# LPCB224_-_POWER_INPUT.net
KiCad netlist of a schematic drawn in Altium Designer
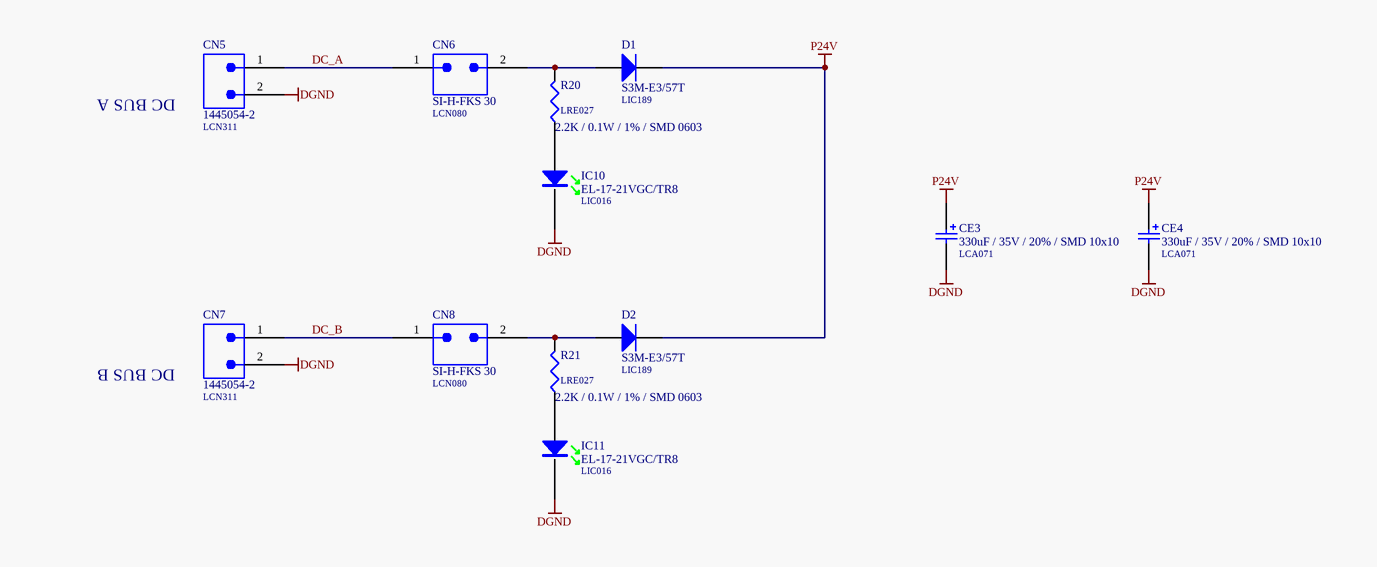
[diagram p0: LPCB224 - POWER INPUT.SchDoc]

(export (version "E")
  (design (tool "Eeschema 10.0.6"))
  (components
    (comp (ref "CE3")
      (value "330uF / 35V / 20% / SMD 10x10")
      (footprint "LFP041__NICHICON_WT_10X10")
      (description "Capacitor, Aluminum Electrolytic, 330uF, 35V, 20%, SMD (10mm x 10mm) [LCA071]")
      (fields (field (name "LDL_NUMBER") "LCA071"))
      (libsource (lib "LDL_Capacitors") (part "330uF / 35V / 20% / SMD 10x10"))
    )
    (comp (ref "CE4")
      (value "330uF / 35V / 20% / SMD 10x10")
      (footprint "LFP041__NICHICON_WT_10X10")
      (description "Capacitor, Aluminum Electrolytic, 330uF, 35V, 20%, SMD (10mm x 10mm) [LCA071]")
      (fields (field (name "LDL_NUMBER") "LCA071"))
      (libsource (lib "LDL_Capacitors") (part "330uF / 35V / 20% / SMD 10x10"))
    )
    (comp (ref "CN5")
      (value "1445054-2")
      (footprint "1445054-2")
      (description "Connector, MATE-N-LOK, Header, 2 Way, PTH")
      (fields (field (name "LDL_NUMBER") "LCN311"))
      (libsource (lib "LDL_Connectors") (part "1445054-2"))
    )
    (comp (ref "CN6")
      (value "SI-H-FKS 30")
      (footprint "SI-H-FKS-30")
      (description "Connector, Blade Fuse Holder, 5mm Terminals, 30A Max, PTH")
      (fields (field (name "LDL_NUMBER") "LCN080"))
      (libsource (lib "LDL_Connectors") (part "SI-H-FKS 30"))
    )
    (comp (ref "CN7")
      (value "1445054-2")
      (footprint "1445054-2")
      (description "Connector, MATE-N-LOK, Header, 2 Way, PTH")
      (fields (field (name "LDL_NUMBER") "LCN311"))
      (libsource (lib "LDL_Connectors") (part "1445054-2"))
    )
    (comp (ref "CN8")
      (value "SI-H-FKS 30")
      (footprint "SI-H-FKS-30")
      (description "Connector, Blade Fuse Holder, 5mm Terminals, 30A Max, PTH")
      (fields (field (name "LDL_NUMBER") "LCN080"))
      (libsource (lib "LDL_Connectors") (part "SI-H-FKS 30"))
    )
    (comp (ref "D1")
      (value "S3M-E3/57T")
      (footprint "LFP040__DO-214AB")
      (description "Diode, General Purpose Rectifier, 3A, 200V, SMD DO-214AB [LIC189]")
      (fields (field (name "LDL_NUMBER") "LIC189"))
      (libsource (lib "LDL_Semiconductors") (part "S3M-E3/57T"))
    )
    (comp (ref "D2")
      (value "S3M-E3/57T")
      (footprint "LFP040__DO-214AB")
      (description "Diode, General Purpose Rectifier, 3A, 200V, SMD DO-214AB [LIC189]")
      (fields (field (name "LDL_NUMBER") "LIC189"))
      (libsource (lib "LDL_Semiconductors") (part "S3M-E3/57T"))
    )
    (comp (ref "IC10")
      (value "EL-17-21VGC/TR8")
      (footprint "CR2012-0805-LED")
      (description "LED, SMD, 0805 Green [LIC016]")
      (fields (field (name "LDL_NUMBER") "LIC016"))
      (libsource (lib "LDL_Semiconductors") (part "EL-17-21VGC/TR8"))
    )
    (comp (ref "IC11")
      (value "EL-17-21VGC/TR8")
      (footprint "CR2012-0805-LED")
      (description "LED, SMD, 0805 Green [LIC016]")
      (fields (field (name "LDL_NUMBER") "LIC016"))
      (libsource (lib "LDL_Semiconductors") (part "EL-17-21VGC/TR8"))
    )
    (comp (ref "R20")
      (value "2.2K / 0.1W / 1% / SMD 0603")
      (footprint "LFP020__CR1608-0603-IPC7351_B")
      (description "Resistor, Ceramic Chip, 2.2K, 0.1W, 1%, SMD 0603 [LRE027]")
      (fields (field (name "LDL_NUMBER") "LRE027"))
      (libsource (lib "LDL_Resistors") (part "2.2K / 0.1W / 1% / SMD 0603"))
    )
    (comp (ref "R21")
      (value "2.2K / 0.1W / 1% / SMD 0603")
      (footprint "LFP020__CR1608-0603-IPC7351_B")
      (description "Resistor, Ceramic Chip, 2.2K, 0.1W, 1%, SMD 0603 [LRE027]")
      (fields (field (name "LDL_NUMBER") "LRE027"))
      (libsource (lib "LDL_Resistors") (part "2.2K / 0.1W / 1% / SMD 0603"))
    )
  )
  (nets
    (net (code "1") (name "/DC_A") (class "Default")
      (node (ref "CN5") (pin "1") (pinfunction "1_1") (pintype "passive"))
      (node (ref "CN6") (pin "1") (pinfunction "1_1") (pintype "passive"))
    )
    (net (code "2") (name "/DC_B") (class "Default")
      (node (ref "CN7") (pin "1") (pinfunction "1_1") (pintype "passive"))
      (node (ref "CN8") (pin "1") (pinfunction "1_1") (pintype "passive"))
    )
    (net (code "3") (name "DGND") (class "Default")
      (node (ref "CE3") (pin "2") (pinfunction "2_2") (pintype "passive"))
      (node (ref "CE4") (pin "2") (pinfunction "2_2") (pintype "passive"))
      (node (ref "CN5") (pin "2") (pinfunction "2_2") (pintype "passive"))
      (node (ref "CN7") (pin "2") (pinfunction "2_2") (pintype "passive"))
      (node (ref "IC10") (pin "K") (pintype "passive"))
      (node (ref "IC11") (pin "K") (pintype "passive"))
    )
    (net (code "4") (name "Net-(D1-A)") (class "Default")
      (node (ref "CN6") (pin "2") (pinfunction "2_2") (pintype "passive"))
      (node (ref "D1") (pin "2") (pinfunction "A_2") (pintype "passive"))
      (node (ref "R20") (pin "2") (pintype "passive"))
    )
    (net (code "5") (name "Net-(D2-A)") (class "Default")
      (node (ref "CN8") (pin "2") (pinfunction "2_2") (pintype "passive"))
      (node (ref "D2") (pin "2") (pinfunction "A_2") (pintype "passive"))
      (node (ref "R21") (pin "2") (pintype "passive"))
    )
    (net (code "6") (name "Net-(IC10-PadA)") (class "Default")
      (node (ref "IC10") (pin "A") (pintype "passive"))
      (node (ref "R20") (pin "1") (pintype "passive"))
    )
    (net (code "7") (name "Net-(IC11-PadA)") (class "Default")
      (node (ref "IC11") (pin "A") (pintype "passive"))
      (node (ref "R21") (pin "1") (pintype "passive"))
    )
    (net (code "8") (name "P24V") (class "Default")
      (node (ref "CE3") (pin "1") (pinfunction "1_1") (pintype "passive"))
      (node (ref "CE4") (pin "1") (pinfunction "1_1") (pintype "passive"))
      (node (ref "D1") (pin "1") (pinfunction "K_1") (pintype "passive"))
      (node (ref "D2") (pin "1") (pinfunction "K_1") (pintype "passive"))
    )
  )
)
